# Microcontroller.net
KiCad netlist of a schematic drawn in Altium Designer
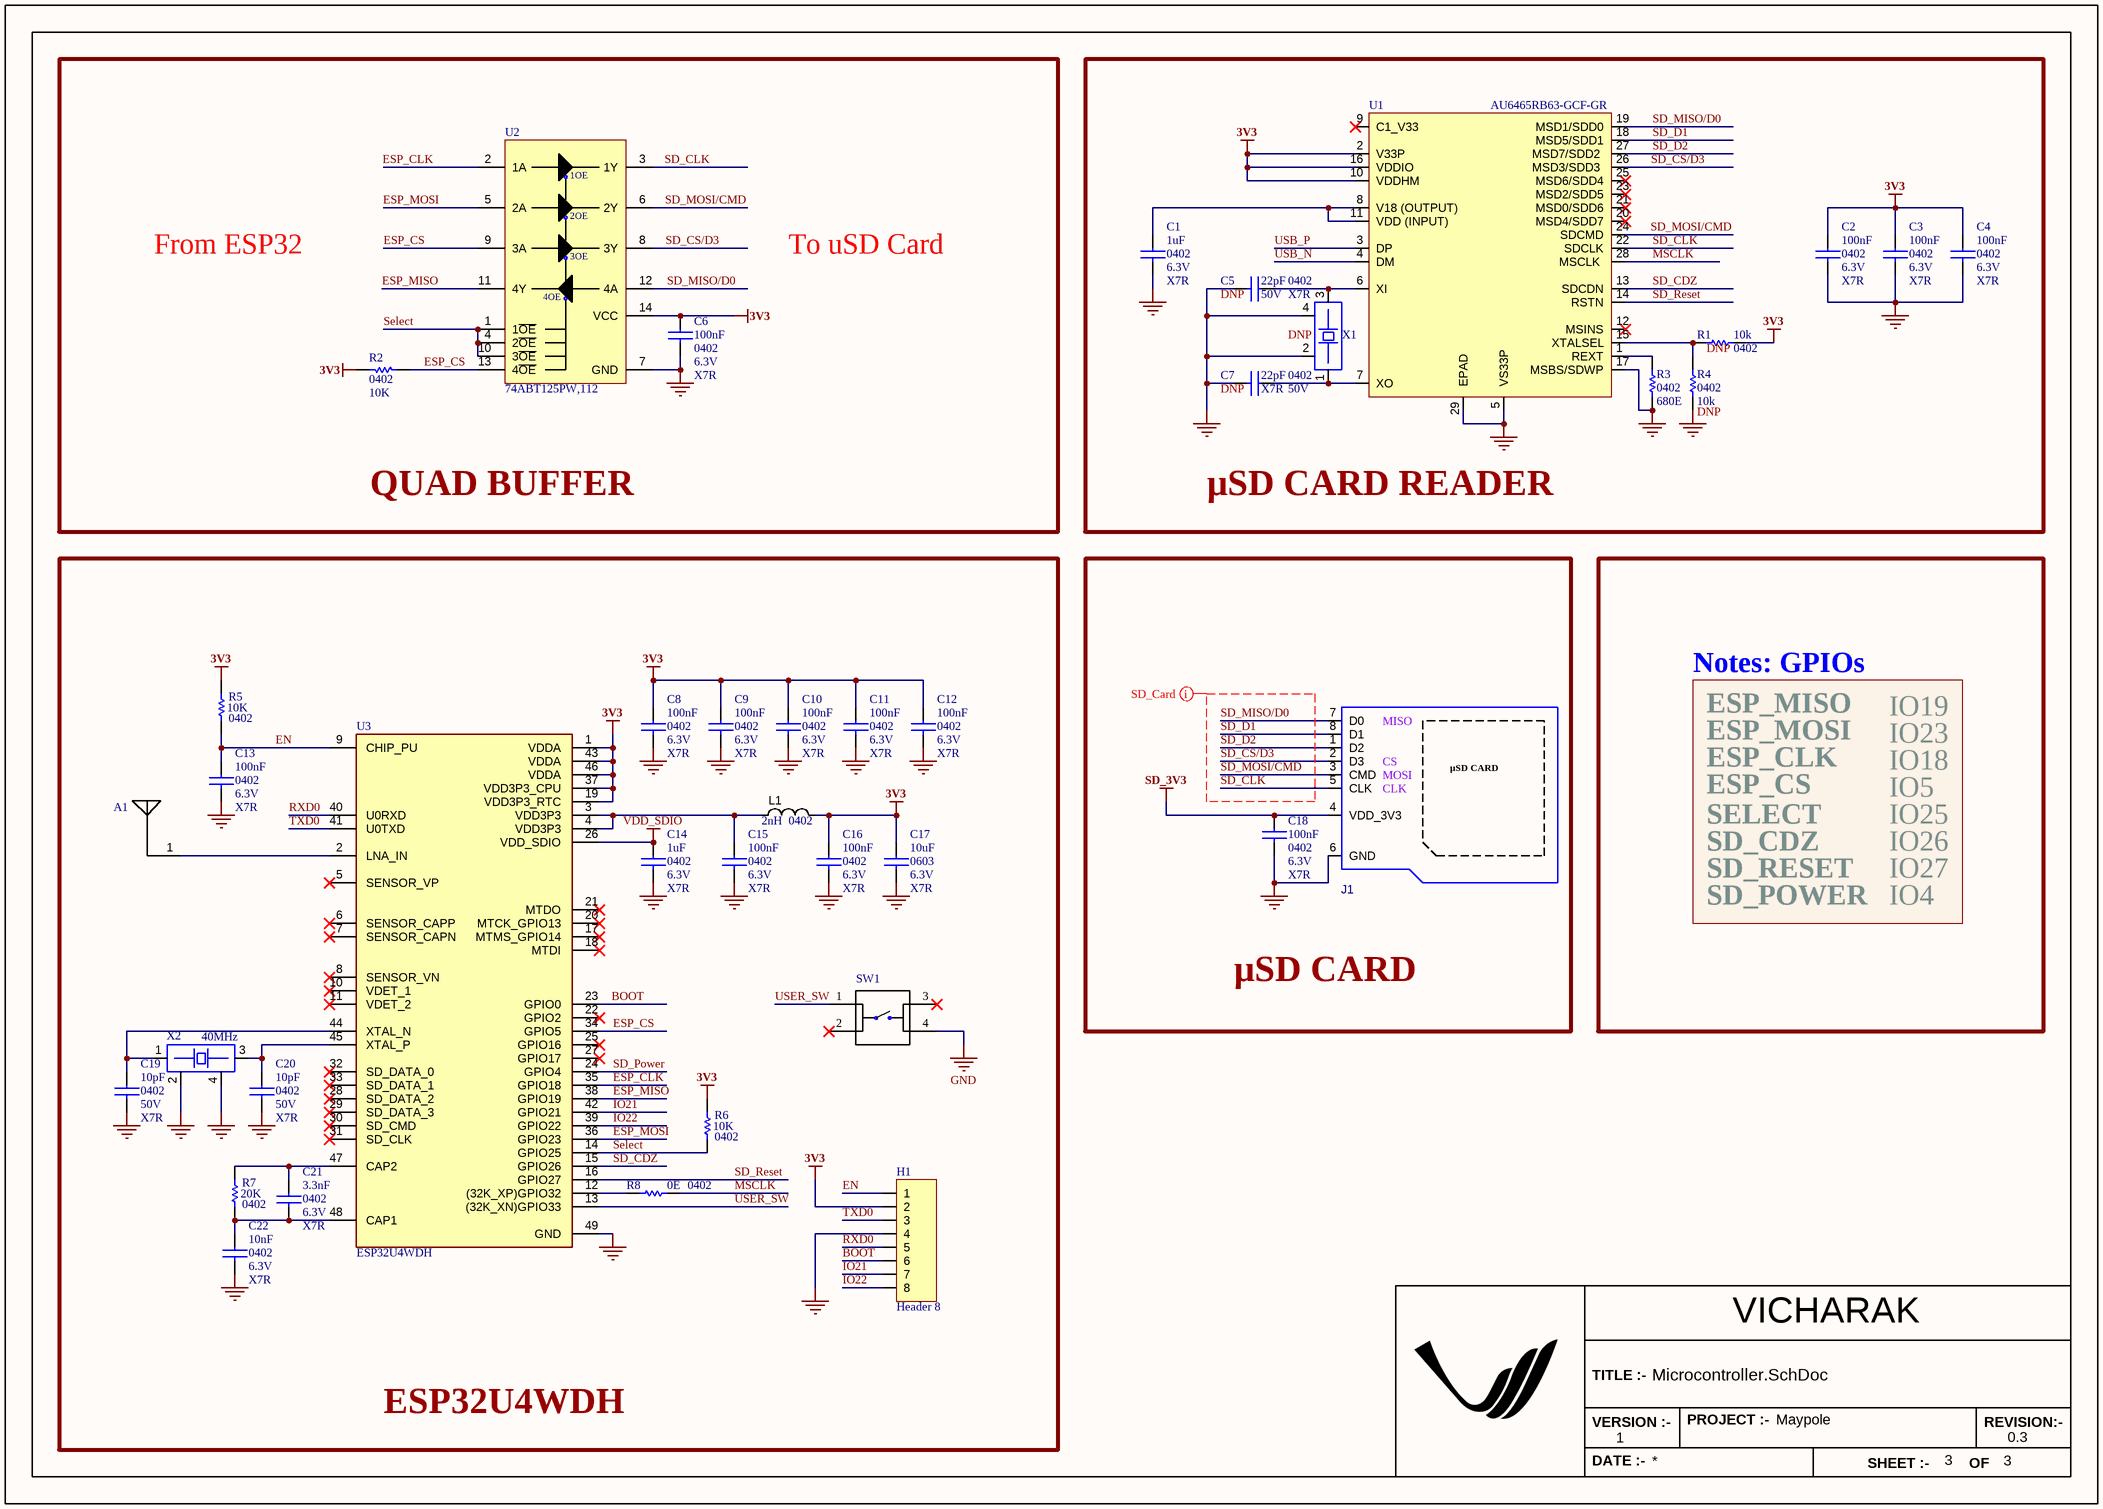
[diagram p0: Microcontroller.SchDoc]

(export (version "E")
  (design (tool "Eeschema 10.0.6"))
  (components
    (comp (ref "A1")
      (value "Ant")
      (footprint "ANT-SMD_L5.2-W2.1")
      (description "SMD,2.1x5.2mm Antennas ROHS")
      (fields (field (name "MANUFACTURER PART NUMBER") "SLDA52-2R710G-S1TF"))
      (libsource (lib "CUSTOM SCH") (part "Ant"))
    )
    (comp (ref "C1")
      (value "1uF")
      (footprint "CAPC0402")
      (description "CAP CER 1uF 6.3V X7R 0402")
      (fields
        (field (name "VOLTAGE") "6.3V")
        (field (name "DIELECTRIC") "X7R")
        (field (name "CASE/PACKAGE") "0402")
      )
      (libsource (lib "CUSTOM SCH") (part "Cap"))
    )
    (comp (ref "C2")
      (value "100nF")
      (footprint "CAPC0402")
      (description "CAP CER 100nF 6.3V X7R 0402")
      (fields
        (field (name "VOLTAGE") "6.3V")
        (field (name "DIELECTRIC") "X7R")
        (field (name "CASE/PACKAGE") "0402")
      )
      (libsource (lib "CUSTOM SCH") (part "Cap"))
    )
    (comp (ref "C3")
      (value "100nF")
      (footprint "CAPC0402")
      (description "CAP CER 100nF 6.3V X7R 0402")
      (fields
        (field (name "VOLTAGE") "6.3V")
        (field (name "DIELECTRIC") "X7R")
        (field (name "CASE/PACKAGE") "0402")
      )
      (libsource (lib "CUSTOM SCH") (part "Cap"))
    )
    (comp (ref "C4")
      (value "100nF")
      (footprint "CAPC0402")
      (description "CAP CER 100nF 6.3V X7R 0402")
      (fields
        (field (name "VOLTAGE") "6.3V")
        (field (name "DIELECTRIC") "X7R")
        (field (name "CASE/PACKAGE") "0402")
      )
      (libsource (lib "CUSTOM SCH") (part "Cap"))
    )
    (comp (ref "C5")
      (value "22pF")
      (footprint "CAPC0402")
      (description "CAP CER 22pF 50V X7R 0402")
      (fields
        (field (name "VOLTAGE") "50V")
        (field (name "DIELECTRIC") "X7R")
        (field (name "CASE/PACKAGE") "0402")
      )
      (libsource (lib "CUSTOM SCH") (part "Cap"))
    )
    (comp (ref "C6")
      (value "100nF")
      (footprint "CAPC0402")
      (description "CAP CER 100nF 6.3V X7R 0402")
      (fields
        (field (name "VOLTAGE") "6.3V")
        (field (name "DIELECTRIC") "X7R")
        (field (name "CASE/PACKAGE") "0402")
      )
      (libsource (lib "CUSTOM SCH") (part "Cap"))
    )
    (comp (ref "C7")
      (value "22pF")
      (footprint "CAPC0402")
      (description "CAP CER 22pF 50V X7R 0402")
      (fields
        (field (name "VOLTAGE") "50V")
        (field (name "DIELECTRIC") "X7R")
        (field (name "CASE/PACKAGE") "0402")
      )
      (libsource (lib "CUSTOM SCH") (part "Cap"))
    )
    (comp (ref "C8")
      (value "100nF")
      (footprint "CAPC0402")
      (description "CAP CER 100nF 6.3V X7R 0402")
      (fields
        (field (name "VOLTAGE") "6.3V")
        (field (name "DIELECTRIC") "X7R")
        (field (name "CASE/PACKAGE") "0402")
      )
      (libsource (lib "CUSTOM SCH") (part "Cap"))
    )
    (comp (ref "C9")
      (value "100nF")
      (footprint "CAPC0402")
      (description "CAP CER 100nF 6.3V X7R 0402")
      (fields
        (field (name "VOLTAGE") "6.3V")
        (field (name "DIELECTRIC") "X7R")
        (field (name "CASE/PACKAGE") "0402")
      )
      (libsource (lib "CUSTOM SCH") (part "Cap"))
    )
    (comp (ref "C10")
      (value "100nF")
      (footprint "CAPC0402")
      (description "CAP CER 100nF 6.3V X7R 0402")
      (fields
        (field (name "VOLTAGE") "6.3V")
        (field (name "DIELECTRIC") "X7R")
        (field (name "CASE/PACKAGE") "0402")
      )
      (libsource (lib "CUSTOM SCH") (part "Cap"))
    )
    (comp (ref "C11")
      (value "100nF")
      (footprint "CAPC0402")
      (description "CAP CER 100nF 6.3V X7R 0402")
      (fields
        (field (name "VOLTAGE") "6.3V")
        (field (name "DIELECTRIC") "X7R")
        (field (name "CASE/PACKAGE") "0402")
      )
      (libsource (lib "CUSTOM SCH") (part "Cap"))
    )
    (comp (ref "C12")
      (value "100nF")
      (footprint "CAPC0402")
      (description "CAP CER 100nF 6.3V X7R 0402")
      (fields
        (field (name "VOLTAGE") "6.3V")
        (field (name "DIELECTRIC") "X7R")
        (field (name "CASE/PACKAGE") "0402")
      )
      (libsource (lib "CUSTOM SCH") (part "Cap"))
    )
    (comp (ref "C13")
      (value "100nF")
      (footprint "CAPC0402")
      (description "CAP CER 100nF 6.3V X7R 0402")
      (fields
        (field (name "VOLTAGE") "6.3V")
        (field (name "DIELECTRIC") "X7R")
        (field (name "CASE/PACKAGE") "0402")
      )
      (libsource (lib "CUSTOM SCH") (part "Cap"))
    )
    (comp (ref "C14")
      (value "1uF")
      (footprint "CAPC0402")
      (description "CAP CER 1uF 6.3V X7R 0402")
      (fields
        (field (name "VOLTAGE") "6.3V")
        (field (name "DIELECTRIC") "X7R")
        (field (name "CASE/PACKAGE") "0402")
      )
      (libsource (lib "CUSTOM SCH") (part "Cap"))
    )
    (comp (ref "C15")
      (value "100nF")
      (footprint "CAPC0402")
      (description "CAP CER 100nF 6.3V X7R 0402")
      (fields
        (field (name "VOLTAGE") "6.3V")
        (field (name "DIELECTRIC") "X7R")
        (field (name "CASE/PACKAGE") "0402")
      )
      (libsource (lib "CUSTOM SCH") (part "Cap"))
    )
    (comp (ref "C16")
      (value "100nF")
      (footprint "CAPC0402")
      (description "CAP CER 100nF 6.3V X7R 0402")
      (fields
        (field (name "VOLTAGE") "6.3V")
        (field (name "DIELECTRIC") "X7R")
        (field (name "CASE/PACKAGE") "0402")
      )
      (libsource (lib "CUSTOM SCH") (part "Cap"))
    )
    (comp (ref "C17")
      (value "10uF")
      (footprint "CAPC0603")
      (description "CAP CER 10uF 6.3V X7R 0603")
      (fields
        (field (name "VOLTAGE") "6.3V")
        (field (name "DIELECTRIC") "X7R")
        (field (name "CASE/PACKAGE") "0603")
      )
      (libsource (lib "CUSTOM SCH") (part "Cap"))
    )
    (comp (ref "C18")
      (value "100nF")
      (footprint "CAPC0402")
      (description "CAP CER 100nF 6.3V X7R 0402")
      (fields
        (field (name "VOLTAGE") "6.3V")
        (field (name "DIELECTRIC") "X7R")
        (field (name "CASE/PACKAGE") "0402")
      )
      (libsource (lib "CUSTOM SCH") (part "Cap"))
    )
    (comp (ref "C19")
      (value "10pF")
      (footprint "CAPC0402")
      (description "CAP CER 10pF 50V X7R 0402")
      (fields
        (field (name "VOLTAGE") "50V")
        (field (name "DIELECTRIC") "X7R")
        (field (name "CASE/PACKAGE") "0402")
      )
      (libsource (lib "CUSTOM SCH") (part "Cap"))
    )
    (comp (ref "C20")
      (value "10pF")
      (footprint "CAPC0402")
      (description "CAP CER 10pF 50V X7R 0402")
      (fields
        (field (name "VOLTAGE") "50V")
        (field (name "DIELECTRIC") "X7R")
        (field (name "CASE/PACKAGE") "0402")
      )
      (libsource (lib "CUSTOM SCH") (part "Cap"))
    )
    (comp (ref "C21")
      (value "3.3nF")
      (footprint "CAPC0402")
      (description "CAP CER 3.3nF 6.3V X7R 0402")
      (fields
        (field (name "VOLTAGE") "6.3V")
        (field (name "DIELECTRIC") "X7R")
        (field (name "CASE/PACKAGE") "0402")
      )
      (libsource (lib "CUSTOM SCH") (part "Cap"))
    )
    (comp (ref "C22")
      (value "10nF")
      (footprint "CAPC0402")
      (description "CAP CER 10nF 6.3V X7R 0402")
      (fields
        (field (name "VOLTAGE") "6.3V")
        (field (name "DIELECTRIC") "X7R")
        (field (name "CASE/PACKAGE") "0402")
      )
      (libsource (lib "CUSTOM SCH") (part "Cap"))
    )
    (comp (ref "H1")
      (value "Header 8")
      (footprint "HEADER_1X08_2.0")
      (description "Header, 08-Pin,2mm")
      (fields (field (name "MANUFACTURER PART NUMBER") "1.27mm PITCH"))
      (libsource (lib "Maypole_V1.2") (part "Header 8"))
    )
    (comp (ref "J1")
      (value "DM3AT-SF-PEJM5(40)")
      (footprint "473521001")
      (description "Micro SD Memory Card Socket")
      (libsource (lib "Maypole_V1.2") (part "DM3AT-SF-PEJM5(40)"))
    )
    (comp (ref "L1")
      (value "~")
      (footprint "IND_0402")
      (description "2nH ±0.3nH 900mA 120mΩ 0402 Inductors (SMD) RoHS")
      (fields
        (field (name "MANUFACTURER PART NUMBER") "LQG15HN2N0S02D")
        (field (name "CASE/PACKAGE") "0402")
        (field (name "INDUCTANCE") "2nH")
      )
      (libsource (lib "Pd's Sch Lib") (part "Inductor"))
    )
    (comp (ref "R1")
      (value "10k")
      (footprint "RESC0402")
      (description "Thick Film Resistor -  10kohm, 1%, 0402")
      (fields (field (name "CASE/PACKAGE") "0402"))
      (libsource (lib "Pd's Sch Lib") (part "Resistor"))
    )
    (comp (ref "R2")
      (value "10K")
      (footprint "RESC0402")
      (description "Thick Film Resistor -  10Kohm, 1%, 0402")
      (fields (field (name "CASE/PACKAGE") "0402"))
      (libsource (lib "Pd's Sch Lib") (part "Resistor"))
    )
    (comp (ref "R3")
      (value "680E")
      (footprint "RESC0402")
      (description "Thick Film Resistor -  680ohm, 1%, 0402")
      (fields (field (name "CASE/PACKAGE") "0402"))
      (libsource (lib "Pd's Sch Lib") (part "Resistor"))
    )
    (comp (ref "R4")
      (value "10k")
      (footprint "RESC0402")
      (description "Thick Film Resistor -  10kohm, 1%, 0402")
      (fields (field (name "CASE/PACKAGE") "0402"))
      (libsource (lib "Pd's Sch Lib") (part "Resistor"))
    )
    (comp (ref "R5")
      (value "10K")
      (footprint "RESC0402")
      (description "Thick Film Resistor -  10Kohm, 1%, 0402")
      (fields (field (name "CASE/PACKAGE") "0402"))
      (libsource (lib "Pd's Sch Lib") (part "Resistor"))
    )
    (comp (ref "R6")
      (value "10K")
      (footprint "RESC0402")
      (description "Thick Film Resistor -  10Kohm, 1%, 0402")
      (fields (field (name "CASE/PACKAGE") "0402"))
      (libsource (lib "Pd's Sch Lib") (part "Resistor"))
    )
    (comp (ref "R7")
      (value "20K")
      (footprint "RESC0402")
      (description "Thick Film Resistor -  20Kohm, 1%, 0402")
      (fields (field (name "CASE/PACKAGE") "0402"))
      (libsource (lib "Pd's Sch Lib") (part "Resistor"))
    )
    (comp (ref "R8")
      (value "0E")
      (footprint "RESC0402")
      (description "Thick Film Resistor -  0ohm, 1%, 0402")
      (fields (field (name "CASE/PACKAGE") "0402"))
      (libsource (lib "Pd's Sch Lib") (part "Resistor"))
    )
    (comp (ref "SW1")
      (value "Button")
      (footprint "RIGHT ANGLE PUSH BUTTON SMD")
      (description "6mm 5mm Round Button 50mA Straight 6mm SPST 12V Plugin Tactile Switches ROHS")
      (fields (field (name "MANUFACTURER PART NUMBER") "TS-1809SM-C"))
      (libsource (lib "Maypole_V1.2") (part "Button"))
    )
    (comp (ref "U1")
      (value "~")
      (footprint "AU6465RB63-GCF-GR")
      (description "Controller QFN-28-EP(5x5) USB ICs ROHS")
      (fields (field (name "MANUFACTURER PART NUMBER") "AU6465RB63-GCF-GR"))
      (libsource (lib "Maypole_V1.1") (part "AU6465RB63-GCF-GR"))
    )
    (comp (ref "U2")
      (value "~")
      (footprint "74ABT125PW")
      (description "Buffers & Line Drivers QUAD BUFFER 3-S")
      (fields (field (name "MANUFACTURER PART NUMBER") "74ABT125PW,112"))
      (libsource (lib "Maypole_V1.1") (part "74ABT125PW_112"))
    )
    (comp (ref "U3")
      (value "~")
      (footprint "QFN48_5X5")
      (description "MCU Bluetooth, WiFi - 2.4GHz 48-QFN")
      (fields
        (field (name "MANUFACTURER") "Espressif Systems")
        (field (name "MANUFACTURER PART NUMBER") "ESP32U4WDH")
      )
      (libsource (lib "Pd's Sch Lib") (part "ESP32-D0WD"))
    )
    (comp (ref "X1")
      (value "~")
      (footprint "CRYSTAL_3225")
      (description "12MHz ±25ppm Crystal 12pF 120 Ohms 4-SMD, No Lead")
      (fields (field (name "MANUFACTURER PART NUMBER") "ECS-120-20-33-TR"))
      (libsource (lib "CUSTOM SCH") (part "CRYSTAL (7M-25.000MEEQ-T)"))
    )
    (comp (ref "X2")
      (value "~")
      (footprint "Crystal_3225")
      (description "40MHz ±10ppm 10pF 30Ω SMD-3225 SMD Crystal Resonators RoHS")
      (fields (field (name "MANUFACTURER PART NUMBER") "7M40000049") (field (name "FREQUENCY") "40MHz"))
      (libsource (lib "Pd's Sch Lib") (part "CRYSTAL_1_1"))
    )
  )
  (nets
    (net (code "1") (name "/BOOT") (class "Default")
      (node (ref "H1") (pin "6") (pinfunction "6_6") (pintype "passive"))
      (node (ref "U3") (pin "23") (pinfunction "GPIO0_23") (pintype "passive"))
    )
    (net (code "2") (name "/EN") (class "Default")
      (node (ref "C13") (pin "1") (pinfunction "1_1") (pintype "passive"))
      (node (ref "H1") (pin "1") (pinfunction "1_1") (pintype "passive"))
      (node (ref "R5") (pin "2") (pinfunction "2_2") (pintype "passive"))
      (node (ref "U3") (pin "9") (pinfunction "CHIP_PU_9") (pintype "passive"))
    )
    (net (code "3") (name "/ESP_CLK") (class "Default")
      (node (ref "U2") (pin "2") (pinfunction "1A_2") (pintype "passive"))
      (node (ref "U3") (pin "35") (pinfunction "GPIO18_35") (pintype "passive"))
    )
    (net (code "4") (name "/ESP_CS") (class "Default")
      (node (ref "R2") (pin "2") (pinfunction "2_2") (pintype "passive"))
      (node (ref "U2") (pin "13") (pinfunction "4~{OE}_13") (pintype "passive"))
      (node (ref "U2") (pin "9") (pinfunction "3A_9") (pintype "passive"))
      (node (ref "U3") (pin "34") (pinfunction "GPIO5_34") (pintype "passive"))
    )
    (net (code "5") (name "/ESP_MISO") (class "Default")
      (node (ref "U2") (pin "11") (pinfunction "4Y_11") (pintype "passive"))
      (node (ref "U3") (pin "38") (pinfunction "GPIO19_38") (pintype "passive"))
    )
    (net (code "6") (name "/ESP_MOSI") (class "Default")
      (node (ref "U2") (pin "5") (pinfunction "2A_5") (pintype "passive"))
      (node (ref "U3") (pin "36") (pinfunction "GPIO23_36") (pintype "passive"))
    )
    (net (code "7") (name "/IO21") (class "Default")
      (node (ref "H1") (pin "7") (pinfunction "7_7") (pintype "passive"))
      (node (ref "U3") (pin "42") (pinfunction "GPIO21_42") (pintype "passive"))
    )
    (net (code "8") (name "/IO22") (class "Default")
      (node (ref "H1") (pin "8") (pinfunction "8_8") (pintype "passive"))
      (node (ref "U3") (pin "39") (pinfunction "GPIO22_39") (pintype "passive"))
    )
    (net (code "9") (name "/MSCLK") (class "Default")
      (node (ref "R8") (pin "1") (pinfunction "1_1") (pintype "passive"))
      (node (ref "U1") (pin "28") (pinfunction "MSCLK_28") (pintype "passive"))
    )
    (net (code "10") (name "/RXD0") (class "Default")
      (node (ref "H1") (pin "5") (pinfunction "5_5") (pintype "passive"))
      (node (ref "U3") (pin "40") (pinfunction "U0RXD_40") (pintype "passive"))
    )
    (net (code "11") (name "/SD_CDZ") (class "Default")
      (node (ref "U1") (pin "13") (pinfunction "SDCDN_13") (pintype "passive"))
      (node (ref "U3") (pin "15") (pinfunction "GPIO26_15") (pintype "passive"))
    )
    (net (code "12") (name "/SD_CLK") (class "Default")
      (node (ref "J1") (pin "5") (pinfunction "CLK_5") (pintype "passive"))
      (node (ref "U1") (pin "22") (pinfunction "SDCLK_22") (pintype "passive"))
      (node (ref "U2") (pin "3") (pinfunction "1Y_3") (pintype "passive"))
    )
    (net (code "13") (name "/SD_CS{slash}D3") (class "Default")
      (node (ref "J1") (pin "2") (pinfunction "D3_2") (pintype "passive"))
      (node (ref "U1") (pin "26") (pinfunction "MSD3/SDD3_26") (pintype "passive"))
      (node (ref "U2") (pin "8") (pinfunction "3Y_8") (pintype "passive"))
    )
    (net (code "14") (name "/SD_D1") (class "Default")
      (node (ref "J1") (pin "8") (pinfunction "D1_8") (pintype "passive"))
      (node (ref "U1") (pin "18") (pinfunction "MSD5/SDD1_18") (pintype "passive"))
    )
    (net (code "15") (name "/SD_D2") (class "Default")
      (node (ref "J1") (pin "1") (pinfunction "D2_1") (pintype "passive"))
      (node (ref "U1") (pin "27") (pinfunction "MSD7/SDD2_27") (pintype "passive"))
    )
    (net (code "16") (name "/SD_MISO{slash}D0") (class "Default")
      (node (ref "J1") (pin "7") (pinfunction "D0_7") (pintype "passive"))
      (node (ref "U1") (pin "19") (pinfunction "MSD1/SDD0_19") (pintype "passive"))
      (node (ref "U2") (pin "12") (pinfunction "4A_12") (pintype "passive"))
    )
    (net (code "17") (name "/SD_MOSI{slash}CMD") (class "Default")
      (node (ref "J1") (pin "3") (pinfunction "CMD_3") (pintype "passive"))
      (node (ref "U1") (pin "24") (pinfunction "SDCMD_24") (pintype "passive"))
      (node (ref "U2") (pin "6") (pinfunction "2Y_6") (pintype "passive"))
    )
    (net (code "18") (name "/SD_Power") (class "Default")
      (node (ref "U3") (pin "24") (pinfunction "GPIO4_24") (pintype "passive"))
    )
    (net (code "19") (name "/SD_Reset") (class "Default")
      (node (ref "U1") (pin "14") (pinfunction "RSTN_14") (pintype "passive"))
      (node (ref "U3") (pin "16") (pinfunction "GPIO27_16") (pintype "passive"))
    )
    (net (code "20") (name "/Select") (class "Default")
      (node (ref "R6") (pin "2") (pinfunction "2_2") (pintype "passive"))
      (node (ref "U2") (pin "1") (pinfunction "1~{OE}_1") (pintype "passive"))
      (node (ref "U2") (pin "10") (pinfunction "3~{OE}_10") (pintype "passive"))
      (node (ref "U2") (pin "4") (pinfunction "2~{OE}_4") (pintype "passive"))
      (node (ref "U3") (pin "14") (pinfunction "GPIO25_14") (pintype "passive"))
    )
    (net (code "21") (name "/TXD0") (class "Default")
      (node (ref "H1") (pin "3") (pinfunction "3_3") (pintype "passive"))
      (node (ref "U3") (pin "41") (pinfunction "U0TXD_41") (pintype "passive"))
    )
    (net (code "22") (name "/USB_N") (class "Default")
      (node (ref "U1") (pin "4") (pinfunction "DM_4") (pintype "passive"))
    )
    (net (code "23") (name "/USB_P") (class "Default")
      (node (ref "U1") (pin "3") (pinfunction "DP_3") (pintype "passive"))
    )
    (net (code "24") (name "/USER_SW") (class "Default")
      (node (ref "SW1") (pin "1") (pinfunction "1_1") (pintype "passive"))
      (node (ref "U3") (pin "13") (pinfunction "(32K_XN)GPIO33_13") (pintype "passive"))
    )
    (net (code "25") (name "3V3") (class "Default")
      (node (ref "C10") (pin "1") (pinfunction "1_1") (pintype "passive"))
      (node (ref "C11") (pin "1") (pinfunction "1_1") (pintype "passive"))
      (node (ref "C12") (pin "1") (pinfunction "1_1") (pintype "passive"))
      (node (ref "C16") (pin "1") (pinfunction "1_1") (pintype "passive"))
      (node (ref "C17") (pin "1") (pinfunction "1_1") (pintype "passive"))
      (node (ref "C2") (pin "1") (pinfunction "1_1") (pintype "passive"))
      (node (ref "C3") (pin "1") (pinfunction "1_1") (pintype "passive"))
      (node (ref "C4") (pin "1") (pinfunction "1_1") (pintype "passive"))
      (node (ref "C6") (pin "1") (pinfunction "1_1") (pintype "passive"))
      (node (ref "C8") (pin "1") (pinfunction "1_1") (pintype "passive"))
      (node (ref "C9") (pin "1") (pinfunction "1_1") (pintype "passive"))
      (node (ref "H1") (pin "2") (pinfunction "2_2") (pintype "passive"))
      (node (ref "L1") (pin "1") (pinfunction "1_1") (pintype "passive"))
      (node (ref "R1") (pin "2") (pinfunction "2_2") (pintype "passive"))
      (node (ref "R2") (pin "1") (pinfunction "1_1") (pintype "passive"))
      (node (ref "R5") (pin "1") (pinfunction "1_1") (pintype "passive"))
      (node (ref "R6") (pin "1") (pinfunction "1_1") (pintype "passive"))
      (node (ref "U1") (pin "10") (pinfunction "VDDHM_10") (pintype "passive"))
      (node (ref "U1") (pin "16") (pinfunction "VDDIO_16") (pintype "passive"))
      (node (ref "U1") (pin "2") (pinfunction "V33P_2") (pintype "passive"))
      (node (ref "U2") (pin "14") (pinfunction "VCC_14") (pintype "passive"))
      (node (ref "U3") (pin "1") (pinfunction "VDDA_1") (pintype "power_in"))
      (node (ref "U3") (pin "19") (pinfunction "VDD3P3_RTC_19") (pintype "power_in"))
      (node (ref "U3") (pin "37") (pinfunction "VDD3P3_CPU_37") (pintype "power_in"))
      (node (ref "U3") (pin "43") (pinfunction "VDDA_43") (pintype "power_in"))
      (node (ref "U3") (pin "46") (pinfunction "VDDA_46") (pintype "power_in"))
    )
    (net (code "26") (name "GND") (class "Default")
      (node (ref "C1") (pin "2") (pinfunction "2_2") (pintype "passive"))
      (node (ref "C10") (pin "2") (pinfunction "2_2") (pintype "passive"))
      (node (ref "C11") (pin "2") (pinfunction "2_2") (pintype "passive"))
      (node (ref "C12") (pin "2") (pinfunction "2_2") (pintype "passive"))
      (node (ref "C13") (pin "2") (pinfunction "2_2") (pintype "passive"))
      (node (ref "C14") (pin "2") (pinfunction "2_2") (pintype "passive"))
      (node (ref "C15") (pin "2") (pinfunction "2_2") (pintype "passive"))
      (node (ref "C16") (pin "2") (pinfunction "2_2") (pintype "passive"))
      (node (ref "C17") (pin "2") (pinfunction "2_2") (pintype "passive"))
      (node (ref "C18") (pin "2") (pinfunction "2_2") (pintype "passive"))
      (node (ref "C19") (pin "2") (pinfunction "2_2") (pintype "passive"))
      (node (ref "C2") (pin "2") (pinfunction "2_2") (pintype "passive"))
      (node (ref "C20") (pin "2") (pinfunction "2_2") (pintype "passive"))
      (node (ref "C22") (pin "2") (pinfunction "2_2") (pintype "passive"))
      (node (ref "C3") (pin "2") (pinfunction "2_2") (pintype "passive"))
      (node (ref "C4") (pin "2") (pinfunction "2_2") (pintype "passive"))
      (node (ref "C5") (pin "2") (pinfunction "2_2") (pintype "passive"))
      (node (ref "C6") (pin "2") (pinfunction "2_2") (pintype "passive"))
      (node (ref "C7") (pin "2") (pinfunction "2_2") (pintype "passive"))
      (node (ref "C8") (pin "2") (pinfunction "2_2") (pintype "passive"))
      (node (ref "C9") (pin "2") (pinfunction "2_2") (pintype "passive"))
      (node (ref "H1") (pin "4") (pinfunction "4_4") (pintype "passive"))
      (node (ref "J1") (pin "6") (pinfunction "GND_6") (pintype "passive"))
      (node (ref "R3") (pin "2") (pinfunction "2_2") (pintype "passive"))
      (node (ref "R4") (pin "2") (pinfunction "2_2") (pintype "passive"))
      (node (ref "SW1") (pin "4") (pinfunction "4_4") (pintype "passive"))
      (node (ref "U1") (pin "17") (pinfunction "MSBS/SDWP_17") (pintype "passive"))
      (node (ref "U1") (pin "29") (pinfunction "EPAD_29") (pintype "passive"))
      (node (ref "U1") (pin "5") (pinfunction "VS33P_5") (pintype "passive"))
      (node (ref "U2") (pin "7") (pinfunction "GND_7") (pintype "passive"))
      (node (ref "U3") (pin "49") (pinfunction "GND_49") (pintype "power_in"))
      (node (ref "X1") (pin "2") (pinfunction "2_2") (pintype "passive"))
      (node (ref "X1") (pin "4") (pinfunction "4_4") (pintype "passive"))
      (node (ref "X2") (pin "2") (pinfunction "2_2") (pintype "passive"))
      (node (ref "X2") (pin "4") (pinfunction "4_4") (pintype "passive"))
    )
    (net (code "27") (name "Net-(A1-Ant)") (class "Default")
      (node (ref "A1") (pin "1") (pinfunction "Ant_1") (pintype "passive"))
      (node (ref "U3") (pin "2") (pinfunction "LNA_IN_2") (pintype "passive"))
    )
    (net (code "28") (name "Net-(C15-Pad1)") (class "Default")
      (node (ref "C15") (pin "1") (pinfunction "1_1") (pintype "passive"))
      (node (ref "L1") (pin "2") (pinfunction "2_2") (pintype "passive"))
      (node (ref "U3") (pin "3") (pinfunction "VDD3P3_3") (pintype "power_in"))
      (node (ref "U3") (pin "4") (pinfunction "VDD3P3_4") (pintype "power_in"))
    )
    (net (code "29") (name "Net-(U1-REXT)") (class "Default")
      (node (ref "R3") (pin "1") (pinfunction "1_1") (pintype "passive"))
      (node (ref "U1") (pin "1") (pinfunction "REXT_1") (pintype "passive"))
    )
    (net (code "30") (name "Net-(U1-V18_(OUTPUT))") (class "Default")
      (node (ref "C1") (pin "1") (pinfunction "1_1") (pintype "passive"))
      (node (ref "U1") (pin "11") (pinfunction "VDD_(INPUT)_11") (pintype "passive"))
      (node (ref "U1") (pin "8") (pinfunction "V18_(OUTPUT)_8") (pintype "passive"))
    )
    (net (code "31") (name "Net-(U1-XI)") (class "Default")
      (node (ref "C5") (pin "1") (pinfunction "1_1") (pintype "passive"))
      (node (ref "U1") (pin "6") (pinfunction "XI_6") (pintype "passive"))
      (node (ref "X1") (pin "3") (pinfunction "3_3") (pintype "passive"))
    )
    (net (code "32") (name "Net-(U1-XO)") (class "Default")
      (node (ref "C7") (pin "1") (pinfunction "1_1") (pintype "passive"))
      (node (ref "U1") (pin "7") (pinfunction "XO_7") (pintype "passive"))
      (node (ref "X1") (pin "1") (pinfunction "1_1") (pintype "passive"))
    )
    (net (code "33") (name "Net-(U1-XTALSEL)") (class "Default")
      (node (ref "R1") (pin "1") (pinfunction "1_1") (pintype "passive"))
      (node (ref "R4") (pin "1") (pinfunction "1_1") (pintype "passive"))
      (node (ref "U1") (pin "15") (pinfunction "XTALSEL_15") (pintype "passive"))
    )
    (net (code "34") (name "Net-(U3-(32K_XP)GPIO32)") (class "Default")
      (node (ref "R8") (pin "2") (pinfunction "2_2") (pintype "passive"))
      (node (ref "U3") (pin "12") (pinfunction "(32K_XP)GPIO32_12") (pintype "passive"))
    )
    (net (code "35") (name "Net-(U3-CAP1)") (class "Default")
      (node (ref "C21") (pin "2") (pinfunction "2_2") (pintype "passive"))
      (node (ref "C22") (pin "1") (pinfunction "1_1") (pintype "passive"))
      (node (ref "R7") (pin "2") (pinfunction "2_2") (pintype "passive"))
      (node (ref "U3") (pin "48") (pinfunction "CAP1_48") (pintype "passive"))
    )
    (net (code "36") (name "Net-(U3-CAP2)") (class "Default")
      (node (ref "C21") (pin "1") (pinfunction "1_1") (pintype "passive"))
      (node (ref "R7") (pin "1") (pinfunction "1_1") (pintype "passive"))
      (node (ref "U3") (pin "47") (pinfunction "CAP2_47") (pintype "passive"))
    )
    (net (code "37") (name "Net-(U3-XTAL_N)") (class "Default")
      (node (ref "C19") (pin "1") (pinfunction "1_1") (pintype "passive"))
      (node (ref "U3") (pin "44") (pinfunction "XTAL_N_44") (pintype "passive"))
      (node (ref "X2") (pin "1") (pinfunction "1_1") (pintype "passive"))
    )
    (net (code "38") (name "Net-(U3-XTAL_P)") (class "Default")
      (node (ref "C20") (pin "1") (pinfunction "1_1") (pintype "passive"))
      (node (ref "U3") (pin "45") (pinfunction "XTAL_P_45") (pintype "passive"))
      (node (ref "X2") (pin "3") (pinfunction "3_3") (pintype "passive"))
    )
    (net (code "39") (name "SD_3V3") (class "Default")
      (node (ref "C18") (pin "1") (pinfunction "1_1") (pintype "passive"))
      (node (ref "J1") (pin "4") (pinfunction "VDD_3V3_4") (pintype "passive"))
    )
    (net (code "40") (name "VDD_SDIO") (class "Default")
      (node (ref "C14") (pin "1") (pinfunction "1_1") (pintype "passive"))
      (node (ref "U3") (pin "26") (pinfunction "VDD_SDIO_26") (pintype "power_in"))
    )
    (net (code "41") (name "unconnected-(SW1-Pad2)") (class "Default")
      (node (ref "SW1") (pin "2") (pinfunction "2_2") (pintype "passive+no_connect"))
    )
    (net (code "42") (name "unconnected-(SW1-Pad3)") (class "Default")
      (node (ref "SW1") (pin "3") (pinfunction "3_3") (pintype "passive+no_connect"))
    )
    (net (code "43") (name "unconnected-(U1-C1_V33-Pad9)") (class "Default")
      (node (ref "U1") (pin "9") (pinfunction "C1_V33_9") (pintype "passive+no_connect"))
    )
    (net (code "44") (name "unconnected-(U1-MSD0{slash}SDD6-Pad21)") (class "Default")
      (node (ref "U1") (pin "21") (pinfunction "MSD0/SDD6_21") (pintype "passive+no_connect"))
    )
    (net (code "45") (name "unconnected-(U1-MSD2{slash}SDD5-Pad23)") (class "Default")
      (node (ref "U1") (pin "23") (pinfunction "MSD2/SDD5_23") (pintype "passive+no_connect"))
    )
    (net (code "46") (name "unconnected-(U1-MSD4{slash}SDD7-Pad20)") (class "Default")
      (node (ref "U1") (pin "20") (pinfunction "MSD4/SDD7_20") (pintype "passive+no_connect"))
    )
    (net (code "47") (name "unconnected-(U1-MSD6{slash}SDD4-Pad25)") (class "Default")
      (node (ref "U1") (pin "25") (pinfunction "MSD6/SDD4_25") (pintype "passive+no_connect"))
    )
    (net (code "48") (name "unconnected-(U1-MSINS-Pad12)") (class "Default")
      (node (ref "U1") (pin "12") (pinfunction "MSINS_12") (pintype "passive+no_connect"))
    )
    (net (code "49") (name "unconnected-(U3-GPIO2-Pad22)") (class "Default")
      (node (ref "U3") (pin "22") (pinfunction "GPIO2_22") (pintype "passive+no_connect"))
    )
    (net (code "50") (name "unconnected-(U3-GPIO16-Pad25)") (class "Default")
      (node (ref "U3") (pin "25") (pinfunction "GPIO16_25") (pintype "passive+no_connect"))
    )
    (net (code "51") (name "unconnected-(U3-GPIO17-Pad27)") (class "Default")
      (node (ref "U3") (pin "27") (pinfunction "GPIO17_27") (pintype "passive+no_connect"))
    )
    (net (code "52") (name "unconnected-(U3-MTCK_GPIO13-Pad20)") (class "Default")
      (node (ref "U3") (pin "20") (pinfunction "MTCK_GPIO13_20") (pintype "passive+no_connect"))
    )
    (net (code "53") (name "unconnected-(U3-MTDI-Pad18)") (class "Default")
      (node (ref "U3") (pin "18") (pinfunction "MTDI_18") (pintype "passive+no_connect"))
    )
    (net (code "54") (name "unconnected-(U3-MTDO-Pad21)") (class "Default")
      (node (ref "U3") (pin "21") (pinfunction "MTDO_21") (pintype "passive+no_connect"))
    )
    (net (code "55") (name "unconnected-(U3-MTMS_GPIO14-Pad17)") (class "Default")
      (node (ref "U3") (pin "17") (pinfunction "MTMS_GPIO14_17") (pintype "passive+no_connect"))
    )
    (net (code "56") (name "unconnected-(U3-SD_CLK-Pad31)") (class "Default")
      (node (ref "U3") (pin "31") (pinfunction "SD_CLK_31") (pintype "passive+no_connect"))
    )
    (net (code "57") (name "unconnected-(U3-SD_CMD-Pad30)") (class "Default")
      (node (ref "U3") (pin "30") (pinfunction "SD_CMD_30") (pintype "passive+no_connect"))
    )
    (net (code "58") (name "unconnected-(U3-SD_DATA_0-Pad32)") (class "Default")
      (node (ref "U3") (pin "32") (pinfunction "SD_DATA_0_32") (pintype "passive+no_connect"))
    )
    (net (code "59") (name "unconnected-(U3-SD_DATA_1-Pad33)") (class "Default")
      (node (ref "U3") (pin "33") (pinfunction "SD_DATA_1_33") (pintype "passive+no_connect"))
    )
    (net (code "60") (name "unconnected-(U3-SD_DATA_2-Pad28)") (class "Default")
      (node (ref "U3") (pin "28") (pinfunction "SD_DATA_2_28") (pintype "passive+no_connect"))
    )
    (net (code "61") (name "unconnected-(U3-SD_DATA_3-Pad29)") (class "Default")
      (node (ref "U3") (pin "29") (pinfunction "SD_DATA_3_29") (pintype "passive+no_connect"))
    )
    (net (code "62") (name "unconnected-(U3-SENSOR_CAPN-Pad7)") (class "Default")
      (node (ref "U3") (pin "7") (pinfunction "SENSOR_CAPN_7") (pintype "passive+no_connect"))
    )
    (net (code "63") (name "unconnected-(U3-SENSOR_CAPP-Pad6)") (class "Default")
      (node (ref "U3") (pin "6") (pinfunction "SENSOR_CAPP_6") (pintype "passive+no_connect"))
    )
    (net (code "64") (name "unconnected-(U3-SENSOR_VN-Pad8)") (class "Default")
      (node (ref "U3") (pin "8") (pinfunction "SENSOR_VN_8") (pintype "passive+no_connect"))
    )
    (net (code "65") (name "unconnected-(U3-SENSOR_VP-Pad5)") (class "Default")
      (node (ref "U3") (pin "5") (pinfunction "SENSOR_VP_5") (pintype "passive+no_connect"))
    )
    (net (code "66") (name "unconnected-(U3-VDET_1-Pad10)") (class "Default")
      (node (ref "U3") (pin "10") (pinfunction "VDET_1_10") (pintype "passive+no_connect"))
    )
    (net (code "67") (name "unconnected-(U3-VDET_2-Pad11)") (class "Default")
      (node (ref "U3") (pin "11") (pinfunction "VDET_2_11") (pintype "passive+no_connect"))
    )
  )
)
